# HelloBoardFinal.net
KiCad netlist of a schematic drawn in EAGLE
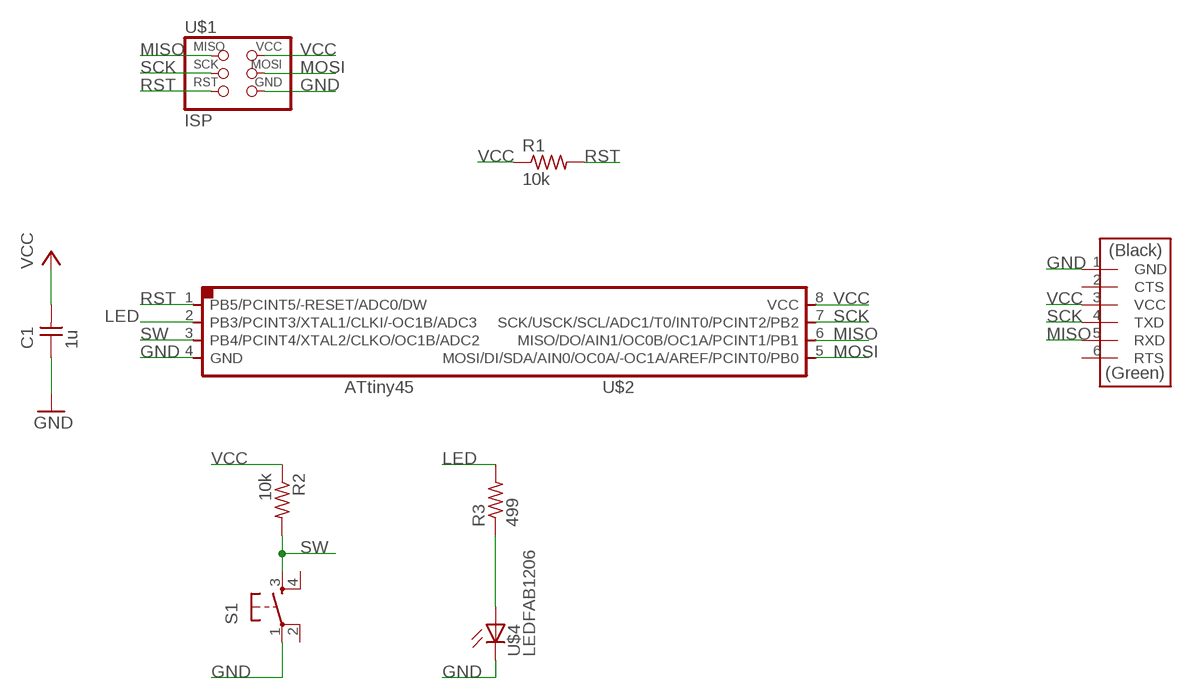
[diagram p0: schematic, sheet 1]

(export (version "E")
  (design (tool "Eeschema 10.0.6"))
  (components
    (comp (ref "C1")
      (value "1u")
      (footprint "eagle-import:C1206FAB")
      (libsource (lib "eagle-import") (part "CAP_UNPOLARIZEDFAB"))
    )
    (comp (ref "R1")
      (value "10k")
      (footprint "eagle-import:R1206FAB")
      (libsource (lib "eagle-import") (part "R1206FAB"))
    )
    (comp (ref "R2")
      (value "10k")
      (footprint "eagle-import:R1206FAB")
      (libsource (lib "eagle-import") (part "R1206FAB"))
    )
    (comp (ref "R3")
      (value "499")
      (footprint "eagle-import:R1206FAB")
      (libsource (lib "eagle-import") (part "R1206FAB"))
    )
    (comp (ref "S1")
      (value "SW_SWITCH_TACTILE_6MM6MM_SWITCH")
      (footprint "eagle-import:6MM_SWITCH")
      (libsource (lib "eagle-import") (part "SW_SWITCH_TACTILE_6MM6MM_SWITCH"))
    )
    (comp (ref "U$1")
      (value "ISP")
      (footprint "eagle-import:2X03SMD")
      (libsource (lib "eagle-import") (part "CONN_03X2_AVRISPSMD"))
    )
    (comp (ref "U$2")
      (value "AT45")
      (footprint "eagle-import:SOIC8")
      (libsource (lib "eagle-import") (part "UC_ATTINY45SI"))
    )
    (comp (ref "U$3")
      (value "CONN_06_FTDI-SMD-HEADER")
      (footprint "eagle-import:1X06SMD")
      (libsource (lib "eagle-import") (part "CONN_06_FTDI-SMD-HEADER"))
    )
    (comp (ref "U$4")
      (value "LEDFAB1206")
      (footprint "eagle-import:LED1206FAB")
      (libsource (lib "eagle-import") (part "LEDFAB1206"))
    )
  )
  (nets
    (net (code "1") (name "/LED") (class "Default")
      (node (ref "R3") (pin "2") (pinfunction "2_2") (pintype "passive"))
      (node (ref "U$2") (pin "2") (pinfunction "PB3/PCINT3/XTAL1/CLKI/-OC1B/ADC3_2") (pintype "bidirectional"))
    )
    (net (code "2") (name "/MISO") (class "Default")
      (node (ref "U$1") (pin "1") (pinfunction "MISO_1") (pintype "passive"))
      (node (ref "U$2") (pin "6") (pinfunction "MISO/DO/AIN1/OC0B/OC1A/PCINT1/PB1_6") (pintype "bidirectional"))
      (node (ref "U$3") (pin "5") (pinfunction "RXD_5") (pintype "bidirectional"))
    )
    (net (code "3") (name "/MOSI") (class "Default")
      (node (ref "U$1") (pin "4") (pinfunction "MOSI_4") (pintype "passive"))
      (node (ref "U$2") (pin "5") (pinfunction "MOSI/DI/SDA/AIN0/OC0A/-OC1A/AREF/PCINT0/PB0_5") (pintype "bidirectional"))
    )
    (net (code "4") (name "/RST") (class "Default")
      (node (ref "R1") (pin "2") (pinfunction "2_2") (pintype "passive"))
      (node (ref "U$1") (pin "5") (pinfunction "RST_5") (pintype "passive"))
      (node (ref "U$2") (pin "1") (pinfunction "PB5/PCINT5/-RESET/ADC0/DW_1") (pintype "bidirectional"))
    )
    (net (code "5") (name "/SCK") (class "Default")
      (node (ref "U$1") (pin "3") (pinfunction "SCK_3") (pintype "passive"))
      (node (ref "U$2") (pin "7") (pinfunction "SCK/USCK/SCL/ADC1/T0/INT0/PCINT2/PB2_7") (pintype "bidirectional"))
      (node (ref "U$3") (pin "4") (pinfunction "TXD_4") (pintype "bidirectional"))
    )
    (net (code "6") (name "/SW") (class "Default")
      (node (ref "R2") (pin "2") (pinfunction "2_2") (pintype "passive"))
      (node (ref "S1") (pin "3") (pinfunction "S_3") (pintype "passive"))
      (node (ref "U$2") (pin "3") (pinfunction "PB4/PCINT4/XTAL2/CLKO/OC1B/ADC2_3") (pintype "bidirectional"))
    )
    (net (code "7") (name "GND") (class "Default")
      (node (ref "C1") (pin "1") (pinfunction "1_1") (pintype "passive"))
      (node (ref "S1") (pin "1") (pinfunction "P_1") (pintype "passive"))
      (node (ref "U$1") (pin "6") (pinfunction "GND_6") (pintype "passive"))
      (node (ref "U$2") (pin "4") (pinfunction "GND_4") (pintype "bidirectional"))
      (node (ref "U$3") (pin "1") (pinfunction "GND_1") (pintype "bidirectional"))
      (node (ref "U$4") (pin "2") (pinfunction "C_2") (pintype "passive"))
    )
    (net (code "8") (name "Net-(U$4-A)") (class "Default")
      (node (ref "R3") (pin "1") (pinfunction "1_1") (pintype "passive"))
      (node (ref "U$4") (pin "1") (pinfunction "A_1") (pintype "passive"))
    )
    (net (code "9") (name "VCC") (class "Default")
      (node (ref "C1") (pin "2") (pinfunction "2_2") (pintype "passive"))
      (node (ref "R1") (pin "1") (pinfunction "1_1") (pintype "passive"))
      (node (ref "R2") (pin "1") (pinfunction "1_1") (pintype "passive"))
      (node (ref "U$1") (pin "2") (pinfunction "VCC_2") (pintype "passive"))
      (node (ref "U$2") (pin "8") (pinfunction "VCC_8") (pintype "bidirectional"))
      (node (ref "U$3") (pin "3") (pinfunction "VCC_3") (pintype "bidirectional"))
    )
    (net (code "10") (name "unconnected-(S1-P1-Pad2)") (class "Default")
      (node (ref "S1") (pin "2") (pinfunction "P1_2") (pintype "passive"))
    )
    (net (code "11") (name "unconnected-(S1-S1-Pad4)") (class "Default")
      (node (ref "S1") (pin "4") (pinfunction "S1_4") (pintype "passive"))
    )
    (net (code "12") (name "unconnected-(U$3-CTS-Pad2)") (class "Default")
      (node (ref "U$3") (pin "2") (pinfunction "CTS_2") (pintype "bidirectional"))
    )
    (net (code "13") (name "unconnected-(U$3-RTS-Pad6)") (class "Default")
      (node (ref "U$3") (pin "6") (pinfunction "RTS_6") (pintype "bidirectional"))
    )
  )
)
